# Shield.net
KiCad netlist of a schematic drawn in EAGLE
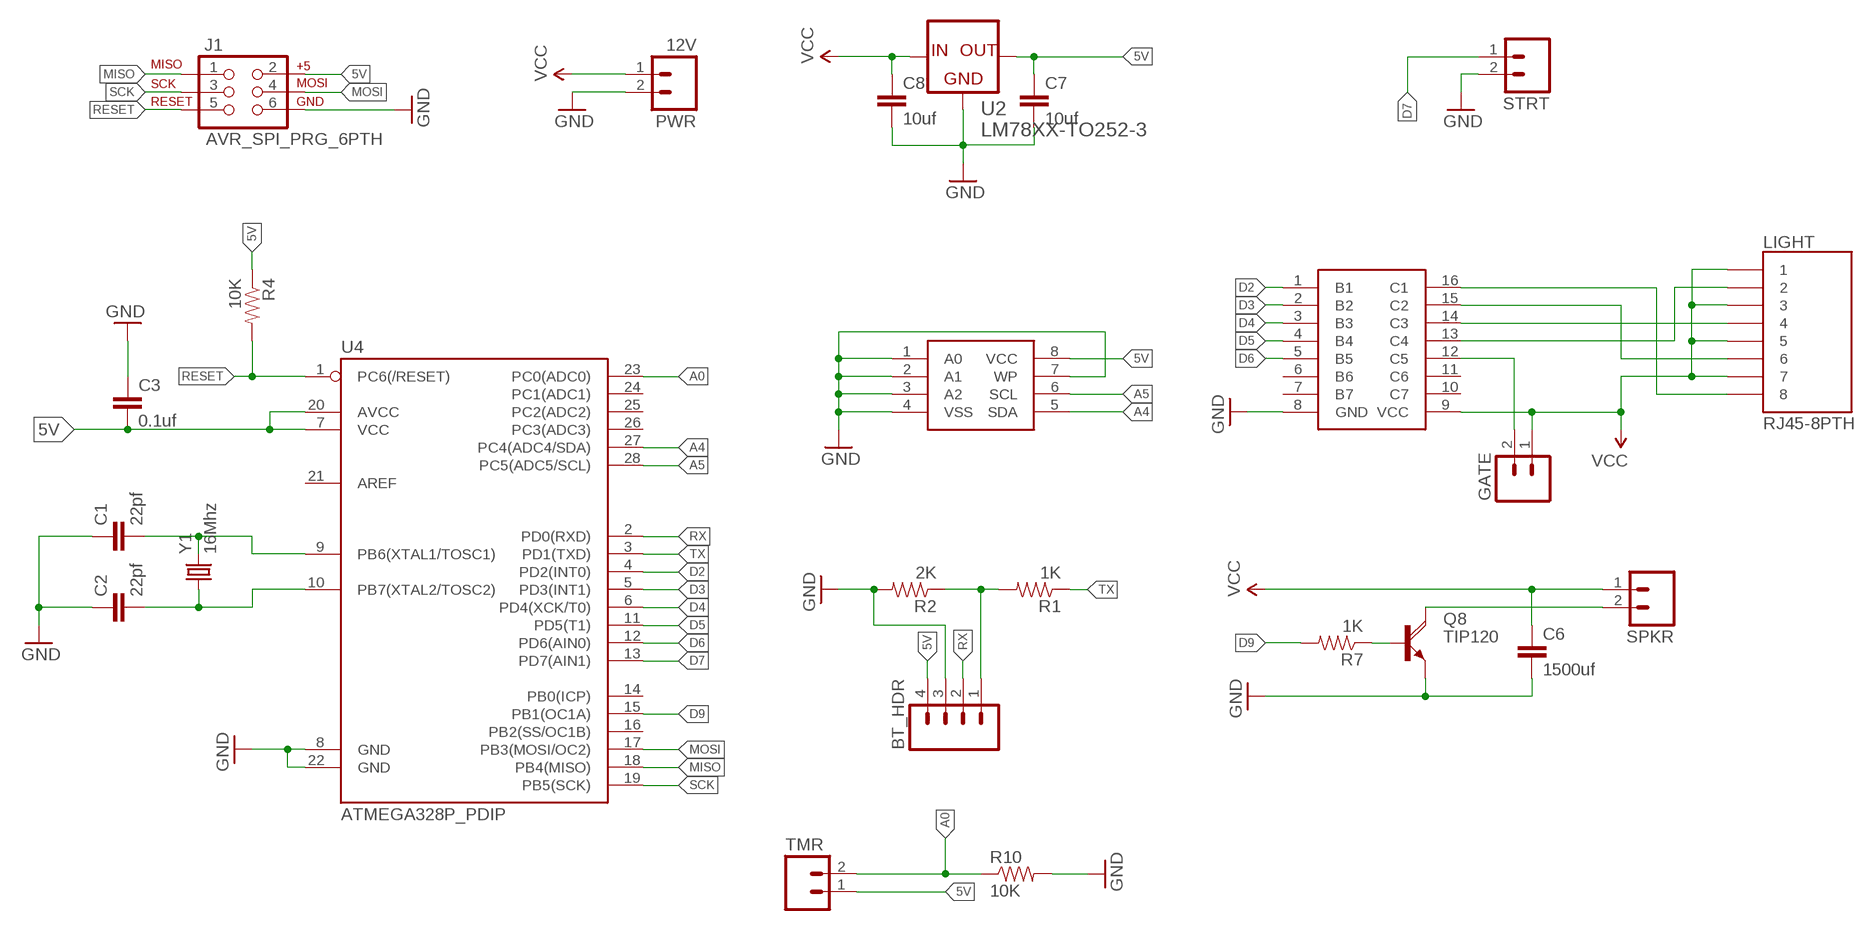
[diagram p0: schematic, sheet 1]

(export (version "E")
  (design (tool "Eeschema 10.0.6"))
  (components
    (comp (ref "BT_HDR")
      (value "M04PTH")
      (footprint "eagle-import:1X04")
      (libsource (lib "eagle-import") (part "M04PTH"))
    )
    (comp (ref "C1")
      (value "22pf")
      (footprint "eagle-import:1206")
      (libsource (lib "eagle-import") (part "CAP1206"))
    )
    (comp (ref "C2")
      (value "22pf")
      (footprint "eagle-import:1206")
      (libsource (lib "eagle-import") (part "CAP1206"))
    )
    (comp (ref "C3")
      (value "0.1uf")
      (footprint "eagle-import:1206")
      (libsource (lib "eagle-import") (part "CAP1206"))
    )
    (comp (ref "C6")
      (value "1500uf")
      (footprint "eagle-import:CAP-PTH-5MM")
      (libsource (lib "eagle-import") (part "CAPPTH1"))
    )
    (comp (ref "C7")
      (value "10uf")
      (footprint "eagle-import:CAP-PTH-SMALL")
      (libsource (lib "eagle-import") (part "CAPPTH"))
    )
    (comp (ref "C8")
      (value "10uf")
      (footprint "eagle-import:CAP-PTH-SMALL")
      (libsource (lib "eagle-import") (part "CAPPTH"))
    )
    (comp (ref "GATE")
      (value "M023.5MM")
      (footprint "eagle-import:SCREWTERMINAL-3.5MM-2")
      (libsource (lib "eagle-import") (part "M023.5MM"))
    )
    (comp (ref "J1")
      (value "AVR_SPI_PRG_6PTH")
      (footprint "eagle-import:2X3")
      (libsource (lib "eagle-import") (part "AVR_SPI_PRG_6PTH"))
    )
    (comp (ref "LIGHT")
      (value "RJ45-8PTH")
      (footprint "eagle-import:RJ45-8")
      (libsource (lib "eagle-import") (part "RJ45-8PTH"))
    )
    (comp (ref "PWR")
      (value "12V")
      (footprint "eagle-import:SCREWTERMINAL-3.5MM-2")
      (libsource (lib "eagle-import") (part "M023.5MM"))
    )
    (comp (ref "Q8")
      (value "TIP120")
      (footprint "eagle-import:TO220V")
      (libsource (lib "eagle-import") (part "TIP120"))
    )
    (comp (ref "R1")
      (value "1K")
      (footprint "eagle-import:1206")
      (libsource (lib "eagle-import") (part "RESISTOR1206"))
    )
    (comp (ref "R2")
      (value "2K")
      (footprint "eagle-import:1206")
      (libsource (lib "eagle-import") (part "RESISTOR1206"))
    )
    (comp (ref "R4")
      (value "10K")
      (footprint "eagle-import:1206")
      (libsource (lib "eagle-import") (part "RESISTOR1206"))
    )
    (comp (ref "R7")
      (value "1K")
      (footprint "eagle-import:1206")
      (libsource (lib "eagle-import") (part "RESISTOR1206"))
    )
    (comp (ref "R10")
      (value "10K")
      (footprint "eagle-import:1206")
      (libsource (lib "eagle-import") (part "RESISTOR1206"))
    )
    (comp (ref "SPKR")
      (value "M023.5MM")
      (footprint "eagle-import:SCREWTERMINAL-3.5MM-2")
      (libsource (lib "eagle-import") (part "M023.5MM"))
    )
    (comp (ref "STRT")
      (value "M023.5MM")
      (footprint "eagle-import:SCREWTERMINAL-3.5MM-2")
      (libsource (lib "eagle-import") (part "M023.5MM"))
    )
    (comp (ref "TMR")
      (value "M023.5MM")
      (footprint "eagle-import:SCREWTERMINAL-3.5MM-2")
      (libsource (lib "eagle-import") (part "M023.5MM"))
    )
    (comp (ref "U$1")
      (value "MC1413D")
      (footprint "eagle-import:SO016")
      (libsource (lib "eagle-import") (part "MC1413D"))
    )
    (comp (ref "U$2")
      (value "24AAXXX")
      (footprint "eagle-import:SOIC-8-EIAJ")
      (libsource (lib "eagle-import") (part "24AAXXX"))
    )
    (comp (ref "U2")
      (value "LM78XX-TO252-3")
      (footprint "eagle-import:TO252-3")
      (fields (field (name "MPN") "UA78M33CKVURG3"))
      (libsource (lib "eagle-import") (part "LM78XX-TO252-3"))
    )
    (comp (ref "U4")
      (value "ATMEGA328P_PDIP")
      (footprint "eagle-import:DIL28-3")
      (libsource (lib "eagle-import") (part "ATMEGA328P_PDIP"))
    )
    (comp (ref "Y1")
      (value "16Mhz")
      (footprint "eagle-import:HC49US")
      (libsource (lib "eagle-import") (part "CRYSTALHC49US"))
    )
  )
  (nets
    (net (code "1") (name "5V") (class "Default")
      (node (ref "BT_HDR") (pin "4") (pinfunction "4_4") (pintype "passive"))
      (node (ref "C3") (pin "2") (pinfunction "2_2") (pintype "passive"))
      (node (ref "C7") (pin "1") (pinfunction "1_1") (pintype "passive"))
      (node (ref "J1") (pin "2") (pinfunction "2_2") (pintype "passive"))
      (node (ref "R4") (pin "1") (pinfunction "1_1") (pintype "passive"))
      (node (ref "TMR") (pin "1") (pinfunction "1_1") (pintype "passive"))
      (node (ref "U$2") (pin "8") (pinfunction "VCC_8") (pintype "bidirectional"))
      (node (ref "U2") (pin "3") (pinfunction "OUT_3") (pintype "output"))
      (node (ref "U4") (pin "20") (pinfunction "AVCC_20") (pintype "bidirectional"))
      (node (ref "U4") (pin "7") (pinfunction "VCC_7") (pintype "bidirectional"))
    )
    (net (code "2") (name "A0") (class "Default")
      (node (ref "R10") (pin "1") (pinfunction "1_1") (pintype "passive"))
      (node (ref "TMR") (pin "2") (pinfunction "2_2") (pintype "passive"))
      (node (ref "U4") (pin "23") (pinfunction "PC0(ADC0)_23") (pintype "bidirectional"))
    )
    (net (code "3") (name "A4") (class "Default")
      (node (ref "U$2") (pin "5") (pinfunction "SDA_5") (pintype "bidirectional"))
      (node (ref "U4") (pin "27") (pinfunction "PC4(ADC4/SDA)_27") (pintype "bidirectional"))
    )
    (net (code "4") (name "A5") (class "Default")
      (node (ref "U$2") (pin "6") (pinfunction "SCL_6") (pintype "bidirectional"))
      (node (ref "U4") (pin "28") (pinfunction "PC5(ADC5/SCL)_28") (pintype "bidirectional"))
    )
    (net (code "5") (name "D2") (class "Default")
      (node (ref "U$1") (pin "1") (pinfunction "B1_1") (pintype "bidirectional"))
      (node (ref "U4") (pin "4") (pinfunction "PD2(INT0)_4") (pintype "bidirectional"))
    )
    (net (code "6") (name "D3") (class "Default")
      (node (ref "U$1") (pin "2") (pinfunction "B2_2") (pintype "bidirectional"))
      (node (ref "U4") (pin "5") (pinfunction "PD3(INT1)_5") (pintype "bidirectional"))
    )
    (net (code "7") (name "D4") (class "Default")
      (node (ref "U$1") (pin "3") (pinfunction "B3_3") (pintype "bidirectional"))
      (node (ref "U4") (pin "6") (pinfunction "PD4(XCK/T0)_6") (pintype "bidirectional"))
    )
    (net (code "8") (name "D5") (class "Default")
      (node (ref "U$1") (pin "4") (pinfunction "B4_4") (pintype "bidirectional"))
      (node (ref "U4") (pin "11") (pinfunction "PD5(T1)_11") (pintype "bidirectional"))
    )
    (net (code "9") (name "D6") (class "Default")
      (node (ref "U$1") (pin "5") (pinfunction "B5_5") (pintype "bidirectional"))
      (node (ref "U4") (pin "12") (pinfunction "PD6(AIN0)_12") (pintype "bidirectional"))
    )
    (net (code "10") (name "D7") (class "Default")
      (node (ref "STRT") (pin "1") (pinfunction "1_1") (pintype "passive"))
      (node (ref "U4") (pin "13") (pinfunction "PD7(AIN1)_13") (pintype "bidirectional"))
    )
    (net (code "11") (name "D9") (class "Default")
      (node (ref "R7") (pin "2") (pinfunction "2_2") (pintype "passive"))
      (node (ref "U4") (pin "15") (pinfunction "PB1(OC1A)_15") (pintype "bidirectional"))
    )
    (net (code "12") (name "GND") (class "Default")
      (node (ref "BT_HDR") (pin "3") (pinfunction "3_3") (pintype "passive"))
      (node (ref "C1") (pin "1") (pinfunction "1_1") (pintype "passive"))
      (node (ref "C2") (pin "1") (pinfunction "1_1") (pintype "passive"))
      (node (ref "C3") (pin "1") (pinfunction "1_1") (pintype "passive"))
      (node (ref "C6") (pin "2") (pinfunction "2_2") (pintype "passive"))
      (node (ref "C7") (pin "2") (pinfunction "2_2") (pintype "passive"))
      (node (ref "C8") (pin "2") (pinfunction "2_2") (pintype "passive"))
      (node (ref "J1") (pin "6") (pinfunction "6_6") (pintype "passive"))
      (node (ref "PWR") (pin "2") (pinfunction "2_2") (pintype "passive"))
      (node (ref "Q8") (pin "3") (pinfunction "E_3") (pintype "passive"))
      (node (ref "R10") (pin "2") (pinfunction "2_2") (pintype "passive"))
      (node (ref "R2") (pin "2") (pinfunction "2_2") (pintype "passive"))
      (node (ref "STRT") (pin "2") (pinfunction "2_2") (pintype "passive"))
      (node (ref "U$1") (pin "8") (pinfunction "GND_8") (pintype "bidirectional"))
      (node (ref "U$2") (pin "1") (pinfunction "A0_1") (pintype "bidirectional"))
      (node (ref "U$2") (pin "2") (pinfunction "A1_2") (pintype "bidirectional"))
      (node (ref "U$2") (pin "3") (pinfunction "A2_3") (pintype "bidirectional"))
      (node (ref "U$2") (pin "4") (pinfunction "VSS_4") (pintype "bidirectional"))
      (node (ref "U$2") (pin "7") (pinfunction "WP_7") (pintype "bidirectional"))
      (node (ref "U2") (pin "2") (pinfunction "COM_2") (pintype "passive"))
      (node (ref "U4") (pin "22") (pinfunction "GND_22") (pintype "bidirectional"))
      (node (ref "U4") (pin "8") (pinfunction "GND_8") (pintype "bidirectional"))
    )
    (net (code "13") (name "MISO") (class "Default")
      (node (ref "J1") (pin "1") (pinfunction "1_1") (pintype "passive"))
      (node (ref "U4") (pin "18") (pinfunction "PB4(MISO)_18") (pintype "bidirectional"))
    )
    (net (code "14") (name "MOSI") (class "Default")
      (node (ref "J1") (pin "4") (pinfunction "4_4") (pintype "passive"))
      (node (ref "U4") (pin "17") (pinfunction "PB3(MOSI/OC2)_17") (pintype "bidirectional"))
    )
    (net (code "15") (name "Net-(BT_HDR-Pad1)") (class "Default")
      (node (ref "BT_HDR") (pin "1") (pinfunction "1_1") (pintype "passive"))
      (node (ref "R1") (pin "2") (pinfunction "2_2") (pintype "passive"))
      (node (ref "R2") (pin "1") (pinfunction "1_1") (pintype "passive"))
    )
    (net (code "16") (name "Net-(Q8-B)") (class "Default")
      (node (ref "Q8") (pin "1") (pinfunction "B_1") (pintype "passive"))
      (node (ref "R7") (pin "1") (pinfunction "1_1") (pintype "passive"))
    )
    (net (code "17") (name "Net-(Q8-C)") (class "Default")
      (node (ref "Q8") (pin "2") (pinfunction "C_2") (pintype "passive"))
      (node (ref "SPKR") (pin "2") (pinfunction "2_2") (pintype "passive"))
    )
    (net (code "18") (name "Net-(U$1-C1)") (class "Default")
      (node (ref "LIGHT") (pin "8") (pinfunction "8_8") (pintype "bidirectional"))
      (node (ref "U$1") (pin "16") (pinfunction "C1_16") (pintype "bidirectional"))
    )
    (net (code "19") (name "Net-(U$1-C2)") (class "Default")
      (node (ref "LIGHT") (pin "6") (pinfunction "6_6") (pintype "bidirectional"))
      (node (ref "U$1") (pin "15") (pinfunction "C2_15") (pintype "bidirectional"))
    )
    (net (code "20") (name "Net-(U$1-C3)") (class "Default")
      (node (ref "LIGHT") (pin "4") (pinfunction "4_4") (pintype "bidirectional"))
      (node (ref "U$1") (pin "14") (pinfunction "C3_14") (pintype "bidirectional"))
    )
    (net (code "21") (name "Net-(U$1-C4)") (class "Default")
      (node (ref "LIGHT") (pin "2") (pinfunction "2_2") (pintype "bidirectional"))
      (node (ref "U$1") (pin "13") (pinfunction "C4_13") (pintype "bidirectional"))
    )
    (net (code "22") (name "Net-(U$1-C5)") (class "Default")
      (node (ref "GATE") (pin "2") (pinfunction "2_2") (pintype "passive"))
      (node (ref "U$1") (pin "12") (pinfunction "C5_12") (pintype "bidirectional"))
    )
    (net (code "23") (name "Net-(U4-PB6(XTAL1{slash}TOSC1))") (class "Default")
      (node (ref "C1") (pin "2") (pinfunction "2_2") (pintype "passive"))
      (node (ref "U4") (pin "9") (pinfunction "PB6(XTAL1/TOSC1)_9") (pintype "bidirectional"))
      (node (ref "Y1") (pin "2") (pinfunction "2_2") (pintype "passive"))
    )
    (net (code "24") (name "Net-(U4-PB7(XTAL2{slash}TOSC2))") (class "Default")
      (node (ref "C2") (pin "2") (pinfunction "2_2") (pintype "passive"))
      (node (ref "U4") (pin "10") (pinfunction "PB7(XTAL2/TOSC2)_10") (pintype "bidirectional"))
      (node (ref "Y1") (pin "1") (pinfunction "1_1") (pintype "passive"))
    )
    (net (code "25") (name "RESET") (class "Default")
      (node (ref "J1") (pin "5") (pinfunction "5_5") (pintype "passive"))
      (node (ref "R4") (pin "2") (pinfunction "2_2") (pintype "passive"))
      (node (ref "U4") (pin "1") (pinfunction "PC6(/RESET)_1") (pintype "bidirectional"))
    )
    (net (code "26") (name "RX") (class "Default")
      (node (ref "BT_HDR") (pin "2") (pinfunction "2_2") (pintype "passive"))
      (node (ref "U4") (pin "2") (pinfunction "PD0(RXD)_2") (pintype "bidirectional"))
    )
    (net (code "27") (name "SCK") (class "Default")
      (node (ref "J1") (pin "3") (pinfunction "3_3") (pintype "passive"))
      (node (ref "U4") (pin "19") (pinfunction "PB5(SCK)_19") (pintype "bidirectional"))
    )
    (net (code "28") (name "TX") (class "Default")
      (node (ref "R1") (pin "1") (pinfunction "1_1") (pintype "passive"))
      (node (ref "U4") (pin "3") (pinfunction "PD1(TXD)_3") (pintype "bidirectional"))
    )
    (net (code "29") (name "VCC") (class "Default")
      (node (ref "C6") (pin "1") (pinfunction "1_1") (pintype "passive"))
      (node (ref "C8") (pin "1") (pinfunction "1_1") (pintype "passive"))
      (node (ref "GATE") (pin "1") (pinfunction "1_1") (pintype "passive"))
      (node (ref "LIGHT") (pin "1") (pinfunction "1_1") (pintype "bidirectional"))
      (node (ref "LIGHT") (pin "3") (pinfunction "3_3") (pintype "bidirectional"))
      (node (ref "LIGHT") (pin "5") (pinfunction "5_5") (pintype "bidirectional"))
      (node (ref "LIGHT") (pin "7") (pinfunction "7_7") (pintype "bidirectional"))
      (node (ref "PWR") (pin "1") (pinfunction "1_1") (pintype "passive"))
      (node (ref "SPKR") (pin "1") (pinfunction "1_1") (pintype "passive"))
      (node (ref "U$1") (pin "9") (pinfunction "VCC_9") (pintype "bidirectional"))
      (node (ref "U2") (pin "1") (pinfunction "IN_1") (pintype "input"))
    )
    (net (code "30") (name "unconnected-(U$1-B6-Pad6)") (class "Default")
      (node (ref "U$1") (pin "6") (pinfunction "B6_6") (pintype "bidirectional"))
    )
    (net (code "31") (name "unconnected-(U$1-B7-Pad7)") (class "Default")
      (node (ref "U$1") (pin "7") (pinfunction "B7_7") (pintype "bidirectional"))
    )
    (net (code "32") (name "unconnected-(U$1-C6-Pad11)") (class "Default")
      (node (ref "U$1") (pin "11") (pinfunction "C6_11") (pintype "bidirectional"))
    )
    (net (code "33") (name "unconnected-(U$1-C7-Pad10)") (class "Default")
      (node (ref "U$1") (pin "10") (pinfunction "C7_10") (pintype "bidirectional"))
    )
    (net (code "34") (name "unconnected-(U4-AREF-Pad21)") (class "Default")
      (node (ref "U4") (pin "21") (pinfunction "AREF_21") (pintype "bidirectional"))
    )
    (net (code "35") (name "unconnected-(U4-PB0(ICP)-Pad14)") (class "Default")
      (node (ref "U4") (pin "14") (pinfunction "PB0(ICP)_14") (pintype "bidirectional"))
    )
    (net (code "36") (name "unconnected-(U4-PB2(SS{slash}OC1B)-Pad16)") (class "Default")
      (node (ref "U4") (pin "16") (pinfunction "PB2(SS/OC1B)_16") (pintype "bidirectional"))
    )
    (net (code "37") (name "unconnected-(U4-PC1(ADC1)-Pad24)") (class "Default")
      (node (ref "U4") (pin "24") (pinfunction "PC1(ADC1)_24") (pintype "bidirectional"))
    )
    (net (code "38") (name "unconnected-(U4-PC2(ADC2)-Pad25)") (class "Default")
      (node (ref "U4") (pin "25") (pinfunction "PC2(ADC2)_25") (pintype "bidirectional"))
    )
    (net (code "39") (name "unconnected-(U4-PC3(ADC3)-Pad26)") (class "Default")
      (node (ref "U4") (pin "26") (pinfunction "PC3(ADC3)_26") (pintype "bidirectional"))
    )
  )
)
